# Tyre_temperature_sensor_PCB.net
KiCad netlist of a schematic drawn in EAGLE
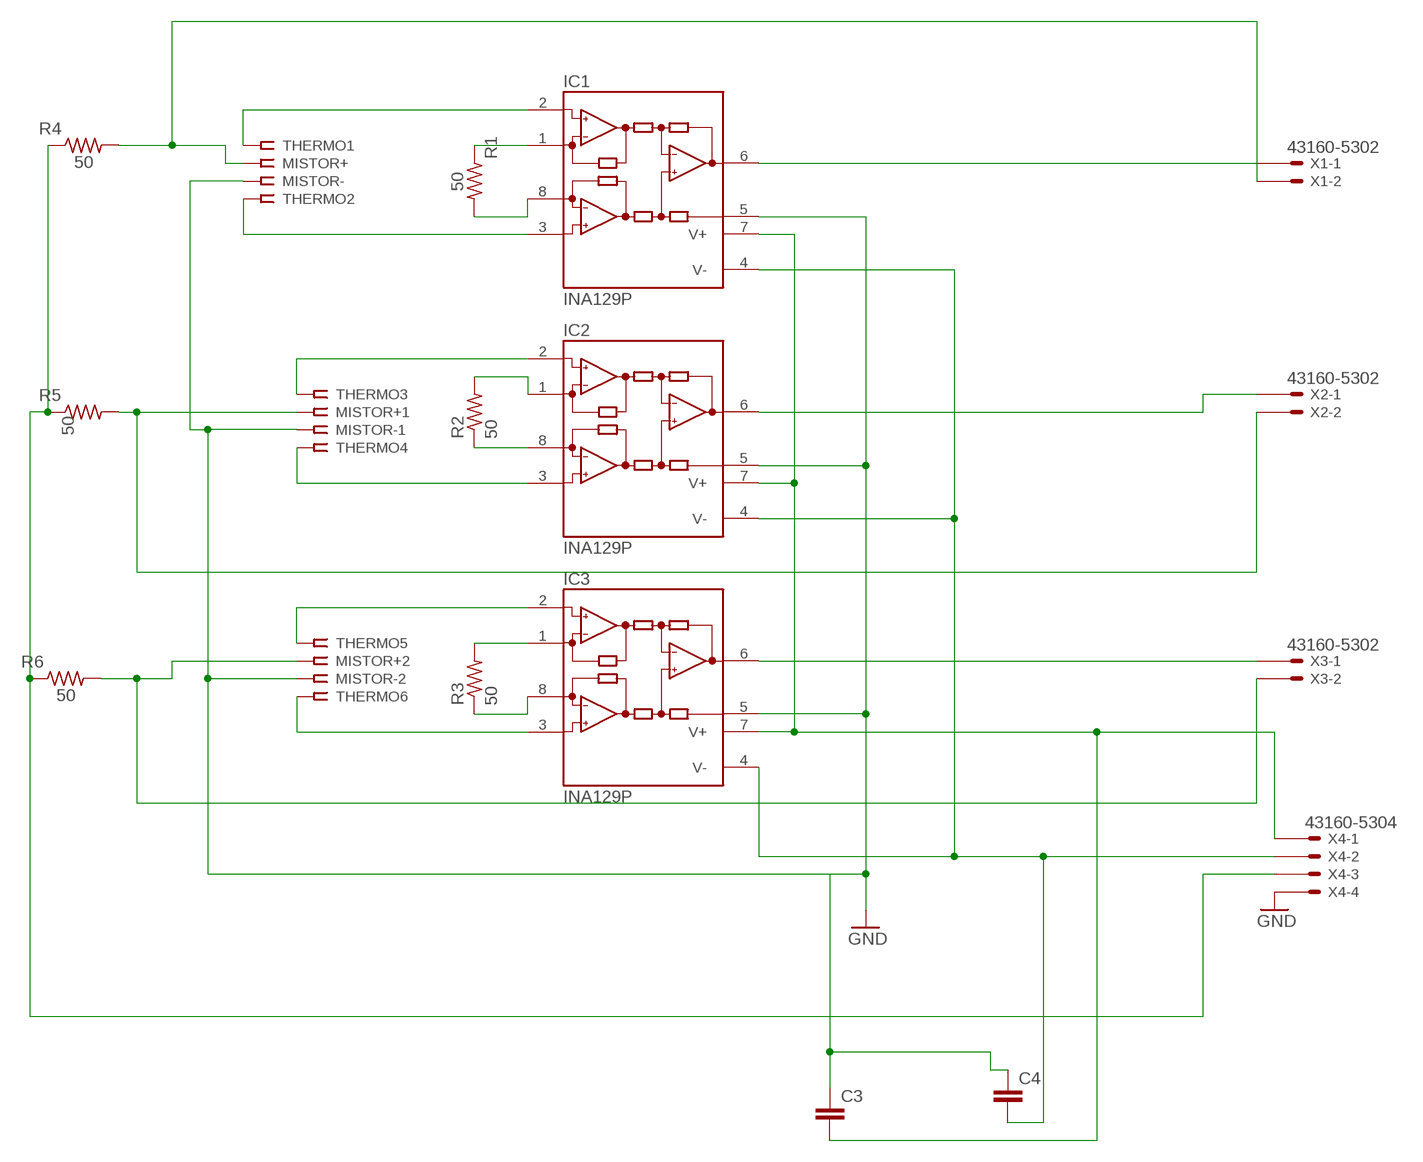
[diagram p0: schematic, sheet 1]

(export (version "E")
  (design (tool "Eeschema 10.0.6"))
  (components
    (comp (ref "C3")
      (value "C5/2.5")
      (footprint "eagle-import:C5B2.5")
      (libsource (lib "eagle-import") (part "C5/2.5"))
    )
    (comp (ref "C4")
      (value "C5/2.5")
      (footprint "eagle-import:C5B2.5")
      (libsource (lib "eagle-import") (part "C5/2.5"))
    )
    (comp (ref "IC1")
      (value "INA129P")
      (footprint "eagle-import:DIL08")
      (fields (field (name "MF") "TEXAS INSTRUMENTS"))
      (libsource (lib "eagle-import") (part "INA129P"))
    )
    (comp (ref "IC2")
      (value "INA129P")
      (footprint "eagle-import:DIL08")
      (fields (field (name "MF") "TEXAS INSTRUMENTS"))
      (libsource (lib "eagle-import") (part "INA129P"))
    )
    (comp (ref "IC3")
      (value "INA129P")
      (footprint "eagle-import:DIL08")
      (fields (field (name "MF") "TEXAS INSTRUMENTS"))
      (libsource (lib "eagle-import") (part "INA129P"))
    )
    (comp (ref "MISTOR+")
      (value "SSW-101-02-G-S")
      (footprint "eagle-import:SSW-101-02-G-S")
      (fields (field (name "MF") "Samtec Inc."))
      (libsource (lib "eagle-import") (part "SSW-101-02-G-S"))
    )
    (comp (ref "MISTOR+1")
      (value "SSW-101-02-G-S")
      (footprint "eagle-import:SSW-101-02-G-S")
      (fields (field (name "MF") "Samtec Inc."))
      (libsource (lib "eagle-import") (part "SSW-101-02-G-S"))
    )
    (comp (ref "MISTOR+2")
      (value "SSW-101-02-G-S")
      (footprint "eagle-import:SSW-101-02-G-S")
      (fields (field (name "MF") "Samtec Inc."))
      (libsource (lib "eagle-import") (part "SSW-101-02-G-S"))
    )
    (comp (ref "MISTOR-")
      (value "SSW-101-02-G-S")
      (footprint "eagle-import:SSW-101-02-G-S")
      (fields (field (name "MF") "Samtec Inc."))
      (libsource (lib "eagle-import") (part "SSW-101-02-G-S"))
    )
    (comp (ref "MISTOR-1")
      (value "SSW-101-02-G-S")
      (footprint "eagle-import:SSW-101-02-G-S")
      (fields (field (name "MF") "Samtec Inc."))
      (libsource (lib "eagle-import") (part "SSW-101-02-G-S"))
    )
    (comp (ref "MISTOR-2")
      (value "SSW-101-02-G-S")
      (footprint "eagle-import:SSW-101-02-G-S")
      (fields (field (name "MF") "Samtec Inc."))
      (libsource (lib "eagle-import") (part "SSW-101-02-G-S"))
    )
    (comp (ref "R1")
      (value "50")
      (footprint "eagle-import:0204_5")
      (libsource (lib "eagle-import") (part "R-US_0204/5"))
    )
    (comp (ref "R2")
      (value "50")
      (footprint "eagle-import:0204_5")
      (libsource (lib "eagle-import") (part "R-US_0204/5"))
    )
    (comp (ref "R3")
      (value "50")
      (footprint "eagle-import:0204_5")
      (libsource (lib "eagle-import") (part "R-US_0204/5"))
    )
    (comp (ref "R4")
      (value "50")
      (footprint "eagle-import:0204_5")
      (libsource (lib "eagle-import") (part "R-US_0204/5"))
    )
    (comp (ref "R5")
      (value "50")
      (footprint "eagle-import:0204_5")
      (libsource (lib "eagle-import") (part "R-US_0204/5"))
    )
    (comp (ref "R6")
      (value "50")
      (footprint "eagle-import:0204_5")
      (libsource (lib "eagle-import") (part "R-US_0204/5"))
    )
    (comp (ref "THERMO1")
      (value "SSW-101-02-G-S")
      (footprint "eagle-import:SSW-101-02-G-S")
      (fields (field (name "MF") "Samtec Inc."))
      (libsource (lib "eagle-import") (part "SSW-101-02-G-S"))
    )
    (comp (ref "THERMO2")
      (value "SSW-101-02-G-S")
      (footprint "eagle-import:SSW-101-02-G-S")
      (fields (field (name "MF") "Samtec Inc."))
      (libsource (lib "eagle-import") (part "SSW-101-02-G-S"))
    )
    (comp (ref "THERMO3")
      (value "SSW-101-02-G-S")
      (footprint "eagle-import:SSW-101-02-G-S")
      (fields (field (name "MF") "Samtec Inc."))
      (libsource (lib "eagle-import") (part "SSW-101-02-G-S"))
    )
    (comp (ref "THERMO4")
      (value "SSW-101-02-G-S")
      (footprint "eagle-import:SSW-101-02-G-S")
      (fields (field (name "MF") "Samtec Inc."))
      (libsource (lib "eagle-import") (part "SSW-101-02-G-S"))
    )
    (comp (ref "THERMO5")
      (value "SSW-101-02-G-S")
      (footprint "eagle-import:SSW-101-02-G-S")
      (fields (field (name "MF") "Samtec Inc."))
      (libsource (lib "eagle-import") (part "SSW-101-02-G-S"))
    )
    (comp (ref "THERMO6")
      (value "SSW-101-02-G-S")
      (footprint "eagle-import:SSW-101-02-G-S")
      (fields (field (name "MF") "Samtec Inc."))
      (libsource (lib "eagle-import") (part "SSW-101-02-G-S"))
    )
    (comp (ref "X1")
      (value "43160-5302")
      (footprint "eagle-import:43160-XX02")
      (fields (field (name "MF") "MOLEX"))
      (libsource (lib "eagle-import") (part "43160-0253"))
    )
    (comp (ref "X2")
      (value "43160-5302")
      (footprint "eagle-import:43160-XX02")
      (fields (field (name "MF") "MOLEX"))
      (libsource (lib "eagle-import") (part "43160-0253"))
    )
    (comp (ref "X3")
      (value "43160-5302")
      (footprint "eagle-import:43160-XX02")
      (fields (field (name "MF") "MOLEX"))
      (libsource (lib "eagle-import") (part "43160-0253"))
    )
    (comp (ref "X4")
      (value "43160-5304")
      (footprint "eagle-import:43160-XX04")
      (fields (field (name "MF") "MOLEX"))
      (libsource (lib "eagle-import") (part "43160-0453"))
    )
  )
  (nets
    (net (code "1") (name "GND") (class "Default")
      (node (ref "C3") (pin "1") (pinfunction "1_1") (pintype "passive"))
      (node (ref "C4") (pin "1") (pinfunction "1_1") (pintype "passive"))
      (node (ref "IC1") (pin "5") (pinfunction "REF_5") (pintype "passive"))
      (node (ref "IC2") (pin "5") (pinfunction "REF_5") (pintype "passive"))
      (node (ref "IC3") (pin "5") (pinfunction "REF_5") (pintype "passive"))
      (node (ref "MISTOR-") (pin "1") (pinfunction "1_1") (pintype "passive"))
      (node (ref "MISTOR-1") (pin "1") (pinfunction "1_1") (pintype "passive"))
      (node (ref "MISTOR-2") (pin "1") (pinfunction "1_1") (pintype "passive"))
      (node (ref "X4") (pin "4@1") (pinfunction "S_4@1") (pintype "passive"))
    )
    (net (code "2") (name "Net-(IC1-+IN)") (class "Default")
      (node (ref "IC1") (pin "3") (pinfunction "+IN_3") (pintype "input"))
      (node (ref "THERMO2") (pin "1") (pinfunction "1_1") (pintype "passive"))
    )
    (net (code "3") (name "Net-(IC1--IN)") (class "Default")
      (node (ref "IC1") (pin "2") (pinfunction "-IN_2") (pintype "input"))
      (node (ref "THERMO1") (pin "1") (pinfunction "1_1") (pintype "passive"))
    )
    (net (code "4") (name "Net-(IC1-OUT)") (class "Default")
      (node (ref "IC1") (pin "6") (pinfunction "OUT_6") (pintype "output"))
      (node (ref "X1") (pin "1@1") (pinfunction "S_1@1") (pintype "passive"))
    )
    (net (code "5") (name "Net-(IC1-RG-Pad1)") (class "Default")
      (node (ref "IC1") (pin "1") (pinfunction "RG_1") (pintype "passive"))
      (node (ref "R1") (pin "1") (pinfunction "1_1") (pintype "passive"))
    )
    (net (code "6") (name "Net-(IC1-RG-Pad8)") (class "Default")
      (node (ref "IC1") (pin "8") (pinfunction "RG_8") (pintype "passive"))
      (node (ref "R1") (pin "2") (pinfunction "2_2") (pintype "passive"))
    )
    (net (code "7") (name "Net-(IC1-V+)") (class "Default")
      (node (ref "C3") (pin "2") (pinfunction "2_2") (pintype "passive"))
      (node (ref "IC1") (pin "7") (pinfunction "V+_7") (pintype "power_in"))
      (node (ref "IC2") (pin "7") (pinfunction "V+_7") (pintype "power_in"))
      (node (ref "IC3") (pin "7") (pinfunction "V+_7") (pintype "power_in"))
      (node (ref "X4") (pin "1@1") (pinfunction "S_1@1") (pintype "passive"))
    )
    (net (code "8") (name "Net-(IC1-V-)") (class "Default")
      (node (ref "C4") (pin "2") (pinfunction "2_2") (pintype "passive"))
      (node (ref "IC1") (pin "4") (pinfunction "V-_4") (pintype "power_in"))
      (node (ref "IC2") (pin "4") (pinfunction "V-_4") (pintype "power_in"))
      (node (ref "IC3") (pin "4") (pinfunction "V-_4") (pintype "power_in"))
      (node (ref "X4") (pin "2@1") (pinfunction "S_2@1") (pintype "passive"))
    )
    (net (code "9") (name "Net-(IC2-+IN)") (class "Default")
      (node (ref "IC2") (pin "3") (pinfunction "+IN_3") (pintype "input"))
      (node (ref "THERMO4") (pin "1") (pinfunction "1_1") (pintype "passive"))
    )
    (net (code "10") (name "Net-(IC2--IN)") (class "Default")
      (node (ref "IC2") (pin "2") (pinfunction "-IN_2") (pintype "input"))
      (node (ref "THERMO3") (pin "1") (pinfunction "1_1") (pintype "passive"))
    )
    (net (code "11") (name "Net-(IC2-OUT)") (class "Default")
      (node (ref "IC2") (pin "6") (pinfunction "OUT_6") (pintype "output"))
      (node (ref "X2") (pin "1@1") (pinfunction "S_1@1") (pintype "passive"))
    )
    (net (code "12") (name "Net-(IC2-RG-Pad1)") (class "Default")
      (node (ref "IC2") (pin "1") (pinfunction "RG_1") (pintype "passive"))
      (node (ref "R2") (pin "2") (pinfunction "2_2") (pintype "passive"))
    )
    (net (code "13") (name "Net-(IC2-RG-Pad8)") (class "Default")
      (node (ref "IC2") (pin "8") (pinfunction "RG_8") (pintype "passive"))
      (node (ref "R2") (pin "1") (pinfunction "1_1") (pintype "passive"))
    )
    (net (code "14") (name "Net-(IC3-+IN)") (class "Default")
      (node (ref "IC3") (pin "3") (pinfunction "+IN_3") (pintype "input"))
      (node (ref "THERMO6") (pin "1") (pinfunction "1_1") (pintype "passive"))
    )
    (net (code "15") (name "Net-(IC3--IN)") (class "Default")
      (node (ref "IC3") (pin "2") (pinfunction "-IN_2") (pintype "input"))
      (node (ref "THERMO5") (pin "1") (pinfunction "1_1") (pintype "passive"))
    )
    (net (code "16") (name "Net-(IC3-OUT)") (class "Default")
      (node (ref "IC3") (pin "6") (pinfunction "OUT_6") (pintype "output"))
      (node (ref "X3") (pin "1@1") (pinfunction "S_1@1") (pintype "passive"))
    )
    (net (code "17") (name "Net-(IC3-RG-Pad1)") (class "Default")
      (node (ref "IC3") (pin "1") (pinfunction "RG_1") (pintype "passive"))
      (node (ref "R3") (pin "2") (pinfunction "2_2") (pintype "passive"))
    )
    (net (code "18") (name "Net-(IC3-RG-Pad8)") (class "Default")
      (node (ref "IC3") (pin "8") (pinfunction "RG_8") (pintype "passive"))
      (node (ref "R3") (pin "1") (pinfunction "1_1") (pintype "passive"))
    )
    (net (code "19") (name "Net-(MISTOR+-Pad1)") (class "Default")
      (node (ref "MISTOR+") (pin "1") (pinfunction "1_1") (pintype "passive"))
      (node (ref "R4") (pin "2") (pinfunction "2_2") (pintype "passive"))
      (node (ref "X1") (pin "2@1") (pinfunction "S_2@1") (pintype "passive"))
    )
    (net (code "20") (name "Net-(MISTOR+1-Pad1)") (class "Default")
      (node (ref "MISTOR+1") (pin "1") (pinfunction "1_1") (pintype "passive"))
      (node (ref "R5") (pin "2") (pinfunction "2_2") (pintype "passive"))
      (node (ref "X2") (pin "2@1") (pinfunction "S_2@1") (pintype "passive"))
    )
    (net (code "21") (name "Net-(MISTOR+2-Pad1)") (class "Default")
      (node (ref "MISTOR+2") (pin "1") (pinfunction "1_1") (pintype "passive"))
      (node (ref "R6") (pin "2") (pinfunction "2_2") (pintype "passive"))
      (node (ref "X3") (pin "2@1") (pinfunction "S_2@1") (pintype "passive"))
    )
    (net (code "22") (name "Net-(R4-Pad1)") (class "Default")
      (node (ref "R4") (pin "1") (pinfunction "1_1") (pintype "passive"))
      (node (ref "R5") (pin "1") (pinfunction "1_1") (pintype "passive"))
      (node (ref "R6") (pin "1") (pinfunction "1_1") (pintype "passive"))
      (node (ref "X4") (pin "3@1") (pinfunction "S_3@1") (pintype "passive"))
    )
    (net (code "23") (name "unconnected-(X1A-S-Pad1@2)") (class "Default")
      (node (ref "X1") (pin "1@2") (pinfunction "S_1@2") (pintype "passive"))
    )
    (net (code "24") (name "unconnected-(X1B-S-Pad2@2)") (class "Default")
      (node (ref "X1") (pin "2@2") (pinfunction "S_2@2") (pintype "passive"))
    )
    (net (code "25") (name "unconnected-(X2A-S-Pad1@2)") (class "Default")
      (node (ref "X2") (pin "1@2") (pinfunction "S_1@2") (pintype "passive"))
    )
    (net (code "26") (name "unconnected-(X2B-S-Pad2@2)") (class "Default")
      (node (ref "X2") (pin "2@2") (pinfunction "S_2@2") (pintype "passive"))
    )
    (net (code "27") (name "unconnected-(X3A-S-Pad1@2)") (class "Default")
      (node (ref "X3") (pin "1@2") (pinfunction "S_1@2") (pintype "passive"))
    )
    (net (code "28") (name "unconnected-(X3B-S-Pad2@2)") (class "Default")
      (node (ref "X3") (pin "2@2") (pinfunction "S_2@2") (pintype "passive"))
    )
    (net (code "29") (name "unconnected-(X4A-S-Pad1@2)") (class "Default")
      (node (ref "X4") (pin "1@2") (pinfunction "S_1@2") (pintype "passive"))
    )
    (net (code "30") (name "unconnected-(X4B-S-Pad2@2)") (class "Default")
      (node (ref "X4") (pin "2@2") (pinfunction "S_2@2") (pintype "passive"))
    )
    (net (code "31") (name "unconnected-(X4C-S-Pad3@2)") (class "Default")
      (node (ref "X4") (pin "3@2") (pinfunction "S_3@2") (pintype "passive"))
    )
    (net (code "32") (name "unconnected-(X4D-S-Pad4@2)") (class "Default")
      (node (ref "X4") (pin "4@2") (pinfunction "S_4@2") (pintype "passive"))
    )
  )
)
